# kiev_nrf2401_reva.net
KiCad netlist of a schematic drawn in EAGLE
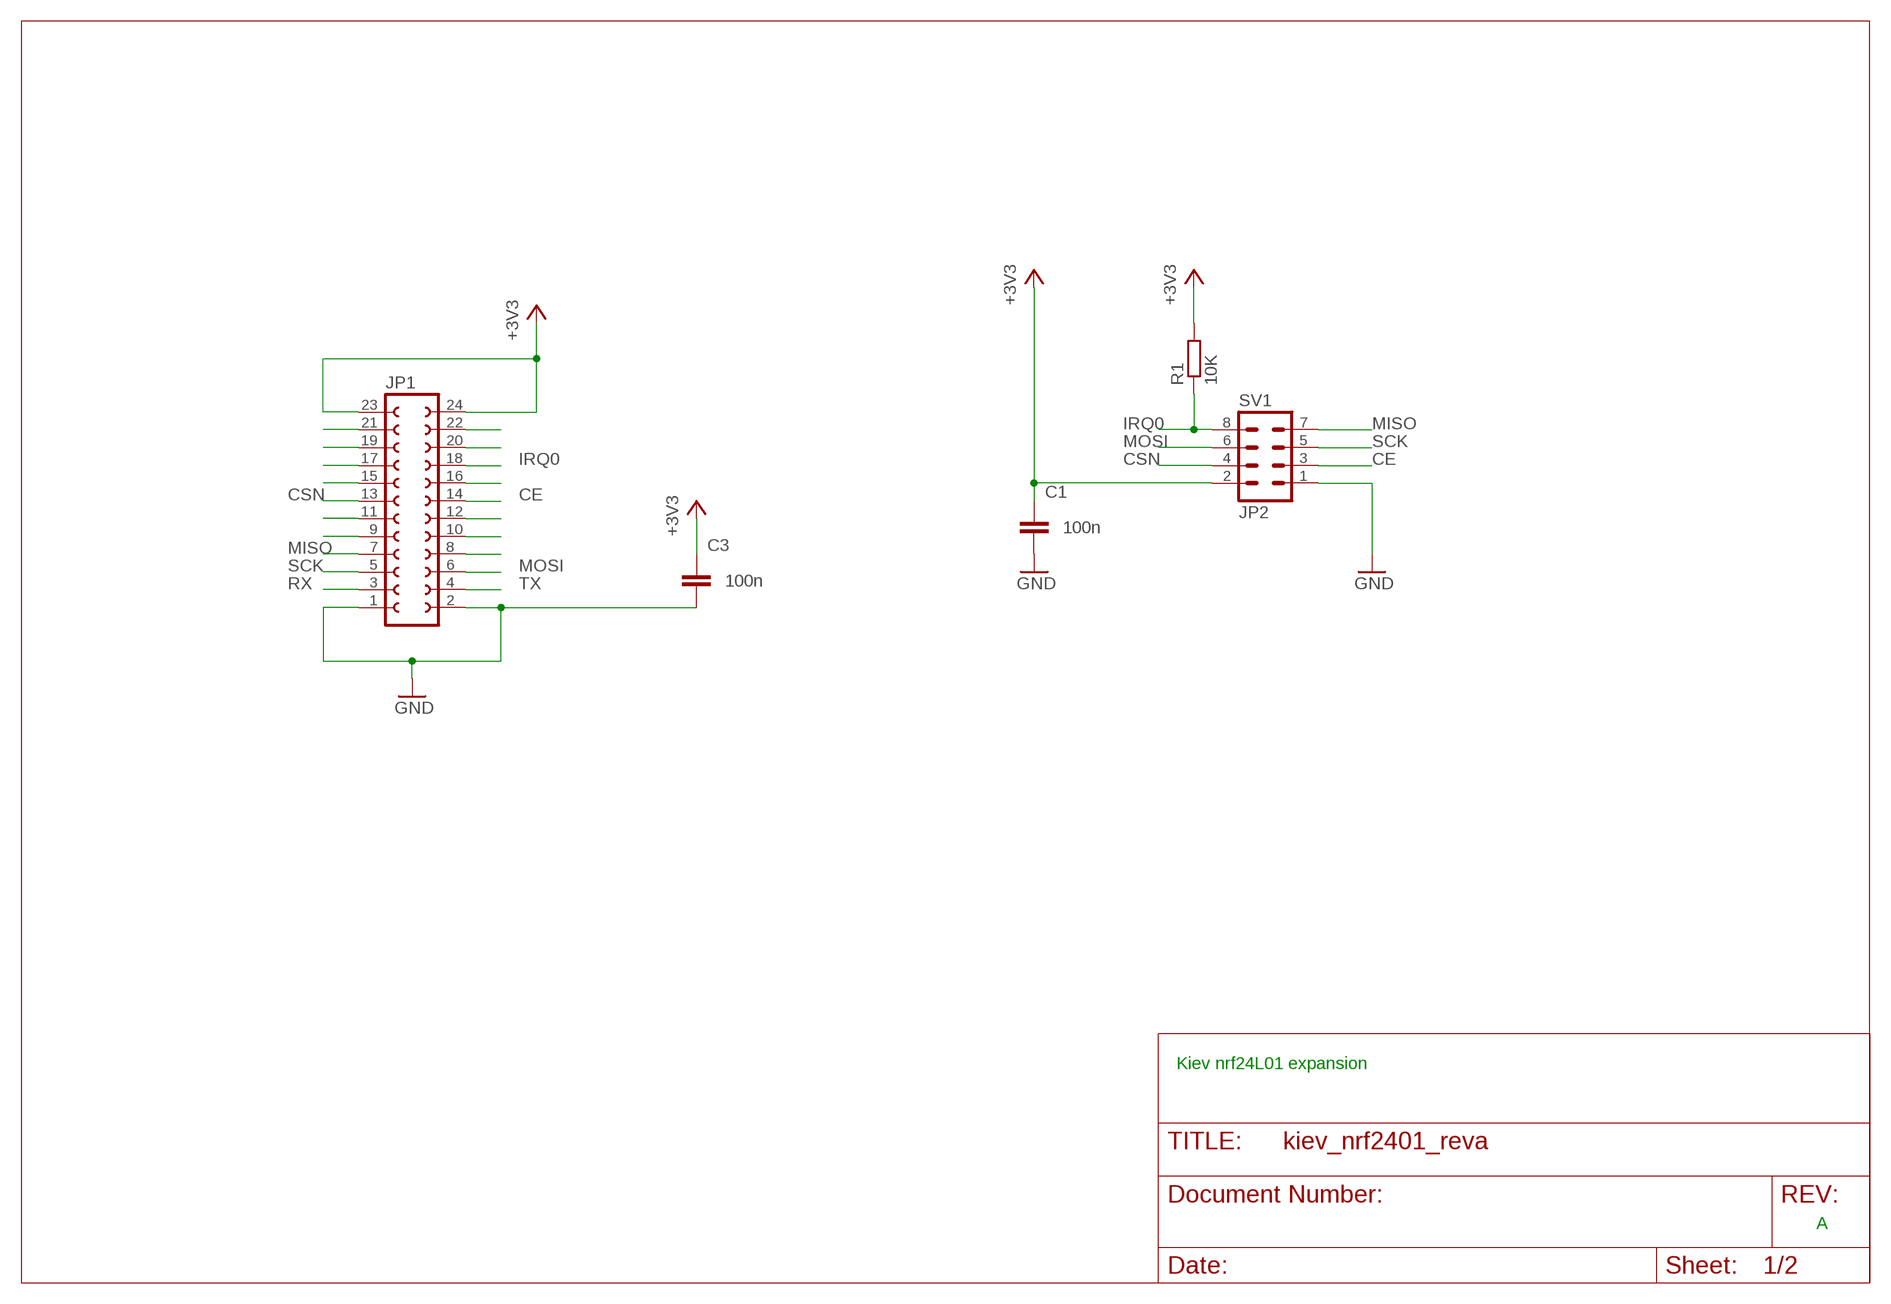
[diagram p0: schematic, sheet 1]
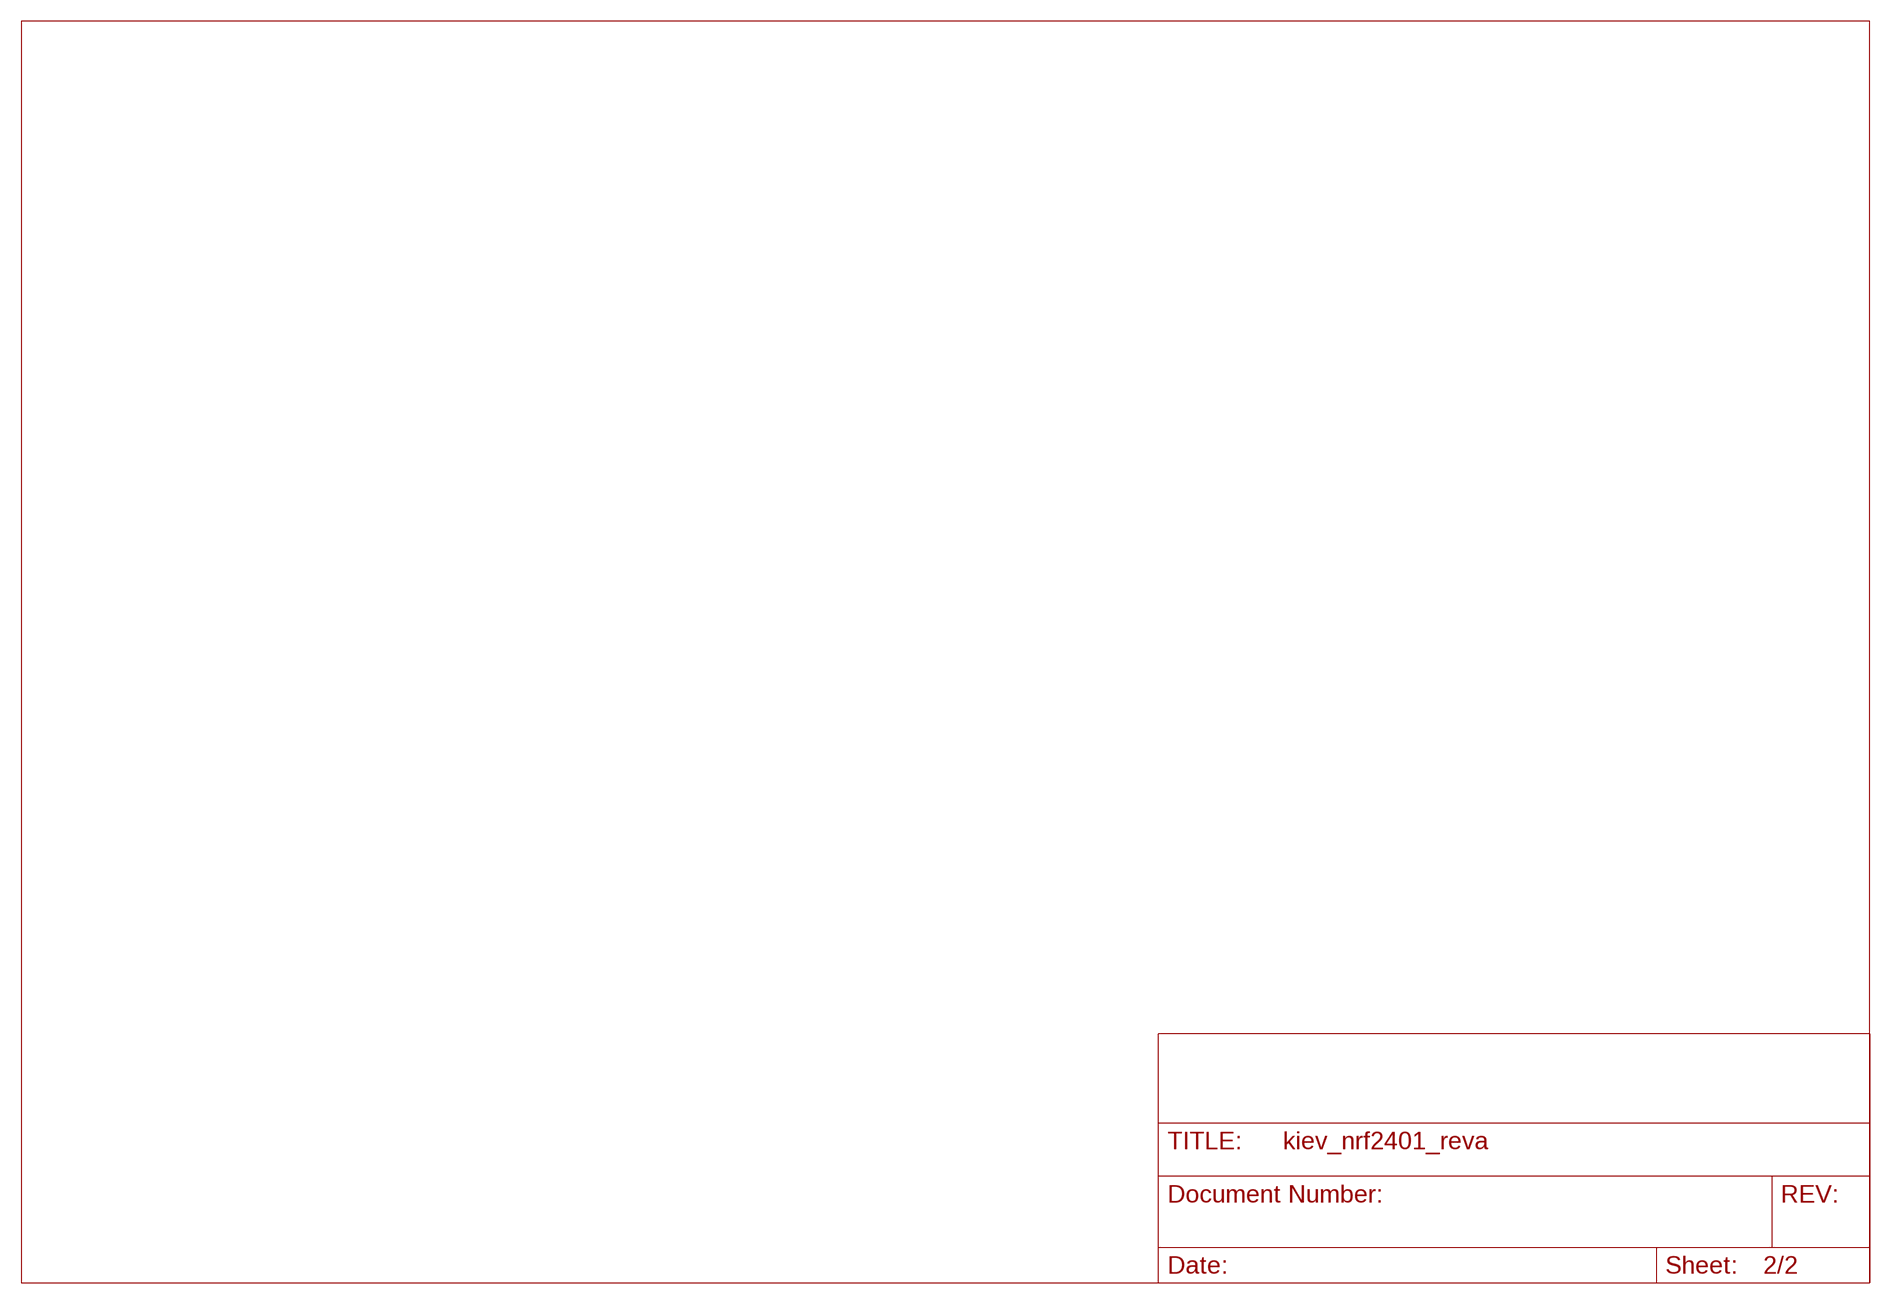
[diagram p1: schematic, sheet 2]

(export (version "E")
  (design (tool "Eeschema 10.0.6"))
  (components
    (comp (ref "C1")
      (value "100n")
      (footprint "eagle-import:C0805")
      (libsource (lib "eagle-import") (part "C-EUC0805"))
    )
    (comp (ref "C3")
      (value "100n")
      (footprint "eagle-import:C0805")
      (libsource (lib "eagle-import") (part "C-EUC0805"))
    )
    (comp (ref "JP1")
      (value "FE12-2")
      (footprint "eagle-import:FE12-2")
      (libsource (lib "eagle-import") (part "FE12-2"))
    )
    (comp (ref "R1")
      (value "10K")
      (footprint "eagle-import:R0805")
      (libsource (lib "eagle-import") (part "R-EU_R0805"))
    )
    (comp (ref "SV1")
      (value "JP2")
      (footprint "eagle-import:MA04-2")
      (libsource (lib "eagle-import") (part "MA04-2"))
    )
  )
  (nets
    (net (code "1") (name "+3V3") (class "Default")
      (node (ref "C1") (pin "1") (pinfunction "1_1") (pintype "passive"))
      (node (ref "C3") (pin "1") (pinfunction "1_1") (pintype "passive"))
      (node (ref "JP1") (pin "23") (pinfunction "23_23") (pintype "passive"))
      (node (ref "JP1") (pin "24") (pinfunction "24_24") (pintype "passive"))
      (node (ref "R1") (pin "2") (pinfunction "2_2") (pintype "passive"))
      (node (ref "SV1") (pin "2") (pinfunction "2_2") (pintype "passive"))
    )
    (net (code "2") (name "CE") (class "Default")
      (node (ref "JP1") (pin "14") (pinfunction "14_14") (pintype "passive"))
      (node (ref "SV1") (pin "3") (pinfunction "3_3") (pintype "passive"))
    )
    (net (code "3") (name "CSN") (class "Default")
      (node (ref "JP1") (pin "13") (pinfunction "13_13") (pintype "passive"))
      (node (ref "SV1") (pin "4") (pinfunction "4_4") (pintype "passive"))
    )
    (net (code "4") (name "GND") (class "Default")
      (node (ref "C1") (pin "2") (pinfunction "2_2") (pintype "passive"))
      (node (ref "C3") (pin "2") (pinfunction "2_2") (pintype "passive"))
      (node (ref "JP1") (pin "1") (pinfunction "1_1") (pintype "passive"))
      (node (ref "JP1") (pin "2") (pinfunction "2_2") (pintype "passive"))
      (node (ref "SV1") (pin "1") (pinfunction "1_1") (pintype "passive"))
    )
    (net (code "5") (name "IRQ0") (class "Default")
      (node (ref "JP1") (pin "18") (pinfunction "18_18") (pintype "passive"))
      (node (ref "R1") (pin "1") (pinfunction "1_1") (pintype "passive"))
      (node (ref "SV1") (pin "8") (pinfunction "8_8") (pintype "passive"))
    )
    (net (code "6") (name "MISO") (class "Default")
      (node (ref "JP1") (pin "7") (pinfunction "7_7") (pintype "passive"))
      (node (ref "SV1") (pin "7") (pinfunction "7_7") (pintype "passive"))
    )
    (net (code "7") (name "MOSI") (class "Default")
      (node (ref "JP1") (pin "6") (pinfunction "6_6") (pintype "passive"))
      (node (ref "SV1") (pin "6") (pinfunction "6_6") (pintype "passive"))
    )
    (net (code "8") (name "RX") (class "Default")
      (node (ref "JP1") (pin "3") (pinfunction "3_3") (pintype "passive"))
    )
    (net (code "9") (name "SCK") (class "Default")
      (node (ref "JP1") (pin "5") (pinfunction "5_5") (pintype "passive"))
      (node (ref "SV1") (pin "5") (pinfunction "5_5") (pintype "passive"))
    )
    (net (code "10") (name "TX") (class "Default")
      (node (ref "JP1") (pin "4") (pinfunction "4_4") (pintype "passive"))
    )
    (net (code "11") (name "unconnected-(JP1-Pad8)") (class "Default")
      (node (ref "JP1") (pin "8") (pinfunction "8_8") (pintype "passive"))
    )
    (net (code "12") (name "unconnected-(JP1-Pad9)") (class "Default")
      (node (ref "JP1") (pin "9") (pinfunction "9_9") (pintype "passive"))
    )
    (net (code "13") (name "unconnected-(JP1-Pad10)") (class "Default")
      (node (ref "JP1") (pin "10") (pinfunction "10_10") (pintype "passive"))
    )
    (net (code "14") (name "unconnected-(JP1-Pad11)") (class "Default")
      (node (ref "JP1") (pin "11") (pinfunction "11_11") (pintype "passive"))
    )
    (net (code "15") (name "unconnected-(JP1-Pad12)") (class "Default")
      (node (ref "JP1") (pin "12") (pinfunction "12_12") (pintype "passive"))
    )
    (net (code "16") (name "unconnected-(JP1-Pad15)") (class "Default")
      (node (ref "JP1") (pin "15") (pinfunction "15_15") (pintype "passive"))
    )
    (net (code "17") (name "unconnected-(JP1-Pad16)") (class "Default")
      (node (ref "JP1") (pin "16") (pinfunction "16_16") (pintype "passive"))
    )
    (net (code "18") (name "unconnected-(JP1-Pad17)") (class "Default")
      (node (ref "JP1") (pin "17") (pinfunction "17_17") (pintype "passive"))
    )
    (net (code "19") (name "unconnected-(JP1-Pad19)") (class "Default")
      (node (ref "JP1") (pin "19") (pinfunction "19_19") (pintype "passive"))
    )
    (net (code "20") (name "unconnected-(JP1-Pad20)") (class "Default")
      (node (ref "JP1") (pin "20") (pinfunction "20_20") (pintype "passive"))
    )
    (net (code "21") (name "unconnected-(JP1-Pad21)") (class "Default")
      (node (ref "JP1") (pin "21") (pinfunction "21_21") (pintype "passive"))
    )
    (net (code "22") (name "unconnected-(JP1-Pad22)") (class "Default")
      (node (ref "JP1") (pin "22") (pinfunction "22_22") (pintype "passive"))
    )
  )
)
